# HapticFeedback.net
KiCad netlist of a schematic drawn in Altium Designer
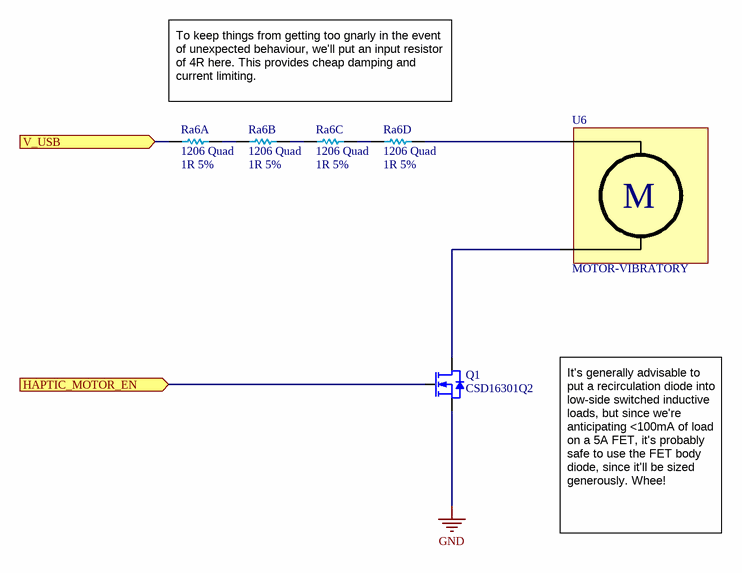
[diagram p0: HapticFeedback.SchDoc]

(export (version "E")
  (design (tool "Eeschema 10.0.6"))
  (components
    (comp (ref "Q1")
      (value "CSD16301Q2")
      (footprint "CSD16301Q2 - SON65P200X80_HS-7M")
      (description "25-V N-Channel Power MOSFET, 20mOhm, 2nC Qg")
      (libsource (lib "FETs") (part "CSD16301Q2"))
    )
    (comp (ref "Ra6")
      (value "1206 Quad")
      (footprint "4x 1R 5% - CAC-80P320X160-8M")
      (description "Chip resistor")
      (fields (field (name "ALTIUM_VALUE") "1R 5%"))
      (libsource (lib "Chip_Passives") (part "Quad Res 1R 5% 1206"))
    )
    (comp (ref "U6")
      (value "MOTOR-VIBRATORY")
      (footprint "MOTOR-VIBRATORY")
      (libsource (lib "Motors") (part "MOTOR-VIBRATORY"))
    )
  )
  (nets
    (net (code "1") (name "/HAPTIC_MOTOR_EN") (class "Default")
      (node (ref "Q1") (pin "G") (pinfunction "G_G") (pintype "passive"))
    )
    (net (code "2") (name "/V_USB") (class "Default")
      (node (ref "Ra6") (pin "1") (pinfunction "1_1") (pintype "passive"))
    )
    (net (code "3") (name "GND") (class "Default")
      (node (ref "Q1") (pin "S") (pinfunction "S_S") (pintype "passive"))
    )
    (net (code "4") (name "Net-(Q1-PadD)") (class "Default")
      (node (ref "Q1") (pin "D") (pinfunction "D_D") (pintype "passive"))
      (node (ref "U6") (pin "2") (pinfunction "2_2") (pintype "passive"))
    )
    (net (code "5") (name "Net-(Ra6-Pad2)") (class "Default")
      (node (ref "Ra6") (pin "2") (pinfunction "2_2") (pintype "passive"))
      (node (ref "Ra6") (pin "8") (pinfunction "8_8") (pintype "passive"))
    )
    (net (code "6") (name "Net-(Ra6-Pad3)") (class "Default")
      (node (ref "Ra6") (pin "3") (pinfunction "3_3") (pintype "passive"))
      (node (ref "Ra6") (pin "7") (pinfunction "7_7") (pintype "passive"))
    )
    (net (code "7") (name "Net-(Ra6-Pad4)") (class "Default")
      (node (ref "Ra6") (pin "4") (pinfunction "4_4") (pintype "passive"))
      (node (ref "Ra6") (pin "6") (pinfunction "6_6") (pintype "passive"))
    )
    (net (code "8") (name "Net-(Ra6-Pad5)") (class "Default")
      (node (ref "Ra6") (pin "5") (pinfunction "5_5") (pintype "passive"))
      (node (ref "U6") (pin "1") (pinfunction "1_1") (pintype "passive"))
    )
  )
)
